# Timed_Power_Switch.net
KiCad netlist of a schematic drawn in Altium Designer
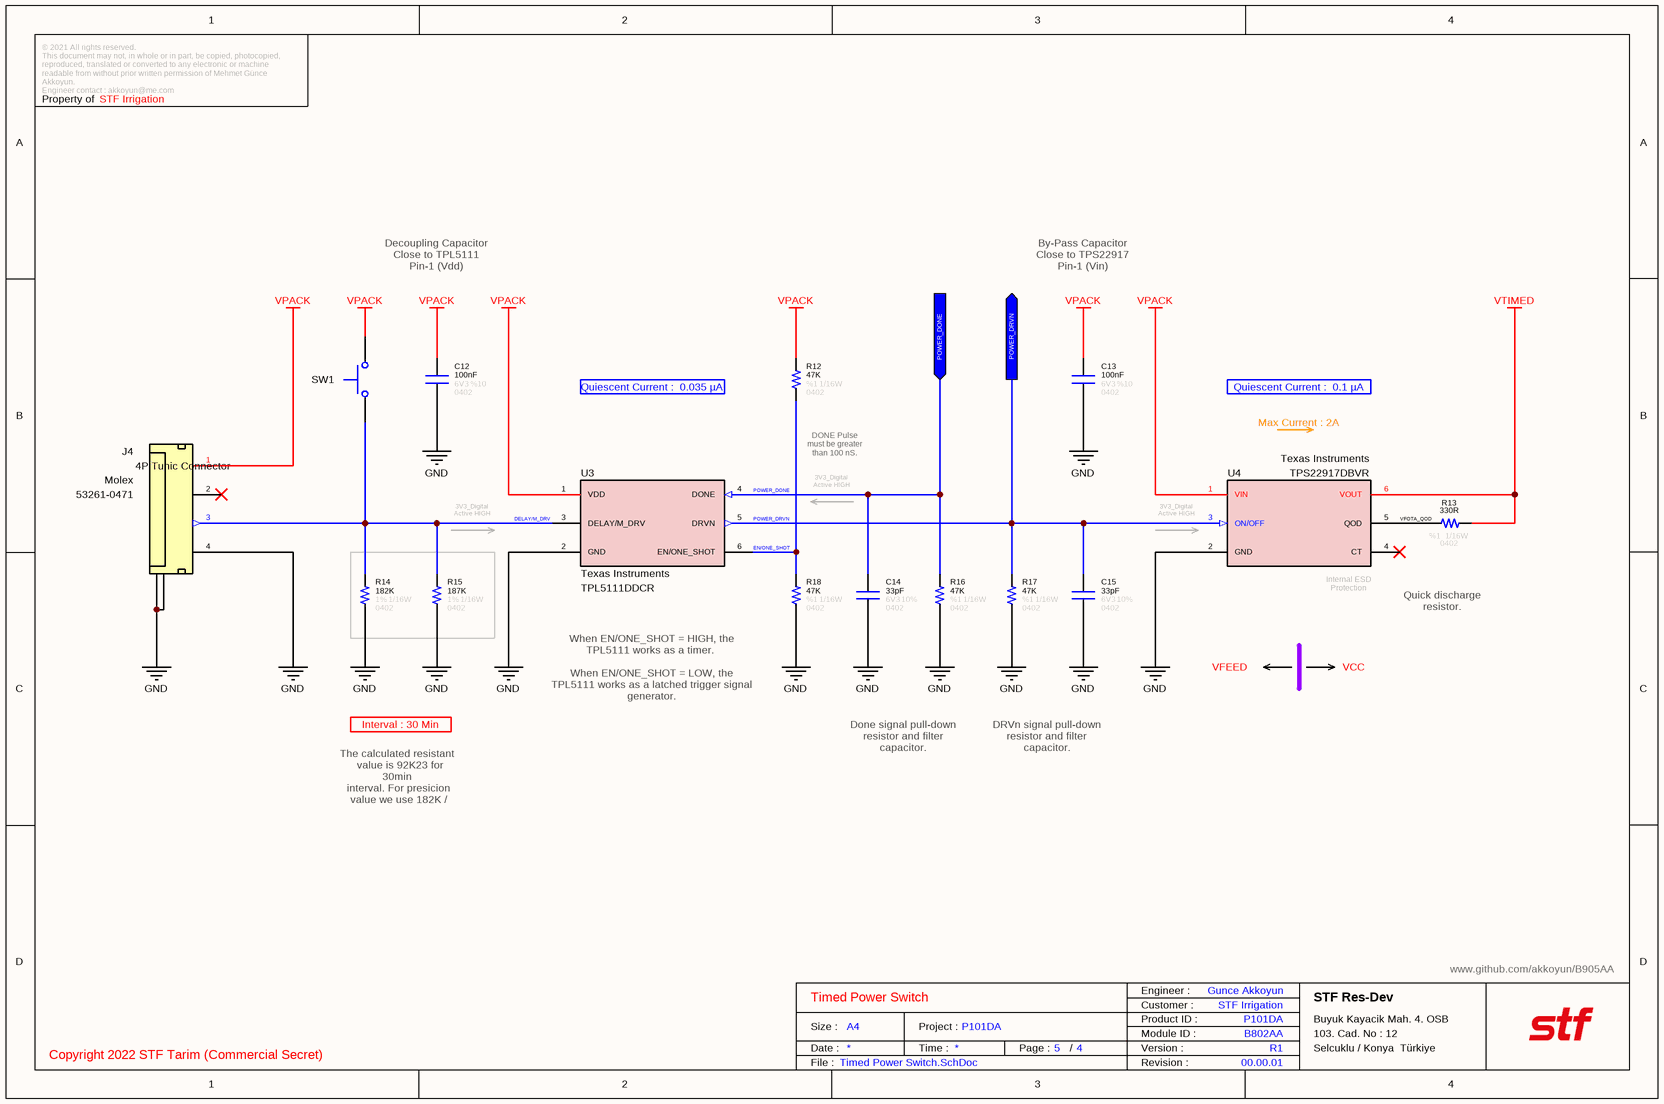
[diagram p0: Timed Power Switch.SchDoc]

(export (version "E")
  (design (tool "Eeschema 10.0.6"))
  (components
    (comp (ref "C12")
      (value "100nF")
      (footprint "CAPACITOR_0402")
      (description "Capacitor - 100nF [0402-6V3] (Ceramic)")
      (fields
        (field (name "MANUFACTURER PART NUMBER") "04026D104KAT4A")
        (field (name "TOLERANCE") "%10")
        (field (name "VOLTAGE") "6V3")
        (field (name "CASE") "0402")
        (field (name "Comment") "Capacitor - 100nF [0402] (Ceramic)")
      )
      (libsource (lib "P101DA_Library") (part "Capacitor - 100nF [0402-6V3]"))
    )
    (comp (ref "C13")
      (value "100nF")
      (footprint "CAPACITOR_0402")
      (description "Capacitor - 100nF [0402-6V3] (Ceramic)")
      (fields
        (field (name "MANUFACTURER PART NUMBER") "04026D104KAT4A")
        (field (name "TOLERANCE") "%10")
        (field (name "VOLTAGE") "6V3")
        (field (name "CASE") "0402")
        (field (name "Comment") "Capacitor - 100nF [0402] (Ceramic)")
      )
      (libsource (lib "P101DA_Library") (part "Capacitor - 100nF [0402-6V3]"))
    )
    (comp (ref "C14")
      (value "33pF")
      (footprint "CAPACITOR_0402")
      (description "Capacitor - 33pF [0402] (Ceramic)")
      (fields
        (field (name "MANUFACTURER PART NUMBER") "C0402C330J9RACAUTO")
        (field (name "TOLERANCE") "10%")
        (field (name "CASE") "0402")
        (field (name "VOLTAGE") "6V3")
      )
      (libsource (lib "P101DA_Library") (part "Capacitor - 33pF [0402-6V3]"))
    )
    (comp (ref "C15")
      (value "33pF")
      (footprint "CAPACITOR_0402")
      (description "Capacitor - 33pF [0402] (Ceramic)")
      (fields
        (field (name "MANUFACTURER PART NUMBER") "C0402C330J9RACAUTO")
        (field (name "TOLERANCE") "10%")
        (field (name "CASE") "0402")
        (field (name "VOLTAGE") "6V3")
      )
      (libsource (lib "P101DA_Library") (part "Capacitor - 33pF [0402-6V3]"))
    )
    (comp (ref "J4")
      (value "4P SMD Tunic Connector")
      (footprint "Connector_Tunic 4P")
      (description "Mini Tunic Connector with 4P")
      (fields
        (field (name "MANUFACTURER NAME") "Molex")
        (field (name "MANUFACTURER PART NUMBER") "53261-0471")
      )
      (libsource (lib "P101DA_Library") (part "Connector - Mini Tunic 4P (1.25)"))
    )
    (comp (ref "R12")
      (value "47K")
      (footprint "RESISTOR_0402")
      (description "Thick Film Resistors - SMD 1/16 W 47 KOhm 1%")
      (fields
        (field (name "MANUFACTURER PART NUMBER") "CRCW040247K0FKED")
        (field (name "TOLERANCE") "%1")
        (field (name "CASE") "0402")
        (field (name "POWER") "1/16W")
        (field (name "Comment") "47K - 0402 - %1 - 1/16W")
      )
      (libsource (lib "P101DA_Library") (part "Resistor - 47K [0402]"))
    )
    (comp (ref "R13")
      (value "330R")
      (footprint "RESISTOR_0402")
      (description "Thick Film Resistors - SMD 1/16 W 330 Ohm 1%")
      (fields
        (field (name "MANUFACTURER PART NUMBER") "CRCW0402330RFKED")
        (field (name "CASE") "0402")
        (field (name "TOLERANCE") "%1")
        (field (name "POWER") "1/16W")
        (field (name "Comment") "330R - 0402 - %1 - 1/16W")
      )
      (libsource (lib "P101DA_Library") (part "Resistor - 330R [0402]"))
    )
    (comp (ref "R14")
      (value "182K")
      (footprint "RESISTOR_0402")
      (description "Thick Film Resistors - SMD 1/16 W 182 KOhm 1%")
      (fields
        (field (name "MANUFACTURER PART NUMBER") "CRCW0402182KFKEDC")
        (field (name "POWER") "1/16W")
        (field (name "CASE") "0402")
        (field (name "TOLERANCE") "1%")
        (field (name "Comment") "182K - 0402 - %1 - 1/16W")
      )
      (libsource (lib "P101DA_Library") (part "Resistor - 182K [0402]"))
    )
    (comp (ref "R15")
      (value "187K")
      (footprint "RESISTOR_0402")
      (description "Thick Film Resistors - SMD 1/16 W 187 KOhm 1%")
      (fields
        (field (name "MANUFACTURER PART NUMBER") "CRCW0402182KFKEDC")
        (field (name "POWER") "1/16W")
        (field (name "CASE") "0402")
        (field (name "TOLERANCE") "1%")
        (field (name "Comment") "187K - 0402 - %1 - 1/16W")
      )
      (libsource (lib "P101DA_Library") (part "Resistor - 187K [0402]"))
    )
    (comp (ref "R16")
      (value "47K")
      (footprint "RESISTOR_0402")
      (description "Thick Film Resistors - SMD 1/16 W 47 KOhm 1%")
      (fields
        (field (name "MANUFACTURER PART NUMBER") "CRCW040247K0FKED")
        (field (name "TOLERANCE") "%1")
        (field (name "CASE") "0402")
        (field (name "POWER") "1/16W")
        (field (name "Comment") "47K - 0402 - %1 - 1/16W")
      )
      (libsource (lib "P101DA_Library") (part "Resistor - 47K [0402]"))
    )
    (comp (ref "R17")
      (value "47K")
      (footprint "RESISTOR_0402")
      (description "Thick Film Resistors - SMD 1/16 W 47 KOhm 1%")
      (fields
        (field (name "MANUFACTURER PART NUMBER") "CRCW040247K0FKED")
        (field (name "TOLERANCE") "%1")
        (field (name "CASE") "0402")
        (field (name "POWER") "1/16W")
        (field (name "Comment") "47K - 0402 - %1 - 1/16W")
      )
      (libsource (lib "P101DA_Library") (part "Resistor - 47K [0402]"))
    )
    (comp (ref "R18")
      (value "47K")
      (footprint "RESISTOR_0402")
      (description "Thick Film Resistors - SMD 1/16 W 47 KOhm 1%")
      (fields
        (field (name "MANUFACTURER PART NUMBER") "CRCW040247K0FKED")
        (field (name "TOLERANCE") "%1")
        (field (name "CASE") "0402")
        (field (name "POWER") "1/16W")
        (field (name "Comment") "47K - 0402 - %1 - 1/16W")
      )
      (libsource (lib "P101DA_Library") (part "Resistor - 47K [0402]"))
    )
    (comp (ref "SW1")
      (value "PTS526SK08SMTR2LFS")
      (footprint "PTS526_Switch")
      (description "Switch Tactile N.O. SPST Flush Round Button Gull Wing 0.05A 12VDC 200000Cycles 2.45N SMD T/R")
      (libsource (lib "P101DA_Library") (part "Switch - Push Button"))
    )
    (comp (ref "U3")
      (value "TPL5111DDCR")
      (footprint "SOT-23-6")
      (description "NANO-POWER SYSTEM TIMER FOR POWE")
      (fields
        (field (name "MANUFACTURER NAME") "Texas Instruments")
        (field (name "MANUFACTURER PART NUMBER") "TPL5111DDCR")
      )
      (libsource (lib "P101DA_Library") (part "IC - TPL5111"))
    )
    (comp (ref "U4")
      (value "Power Switch")
      (footprint "SOT-23-6")
      (description "Power Switch MosFet")
      (fields
        (field (name "MANUFACTURER PART NUMBER") "TPS22917DBVR")
        (field (name "MANUFACTURER NAME") "Texas Instruments")
      )
      (libsource (lib "P101DA_Library") (part "IC - TPS22917"))
    )
  )
  (nets
    (net (code "1") (name "/DELAY{slash}M_DRV") (class "Default")
      (node (ref "J4") (pin "3") (pinfunction "Pin-3_3") (pintype "output"))
      (node (ref "R14") (pin "2") (pinfunction "2_2") (pintype "passive"))
      (node (ref "R15") (pin "2") (pinfunction "2_2") (pintype "passive"))
      (node (ref "SW1") (pin "1") (pinfunction "NC_1") (pintype "passive"))
      (node (ref "U3") (pin "3") (pinfunction "DELAY/M_DRV_3") (pintype "passive"))
    )
    (net (code "2") (name "/EN{slash}ONE_SHOT") (class "Default")
      (node (ref "R12") (pin "1") (pinfunction "1_1") (pintype "passive"))
      (node (ref "R18") (pin "2") (pinfunction "2_2") (pintype "passive"))
      (node (ref "U3") (pin "6") (pinfunction "EN/ONE_SHOT_6") (pintype "passive"))
    )
    (net (code "3") (name "/POWER_DONE") (class "Default")
      (node (ref "C14") (pin "2") (pinfunction "2_2") (pintype "passive"))
      (node (ref "R16") (pin "2") (pinfunction "2_2") (pintype "passive"))
      (node (ref "U3") (pin "4") (pinfunction "DONE_4") (pintype "input"))
    )
    (net (code "4") (name "/POWER_DRVN") (class "Default")
      (node (ref "C15") (pin "2") (pinfunction "2_2") (pintype "passive"))
      (node (ref "R17") (pin "2") (pinfunction "2_2") (pintype "passive"))
      (node (ref "U3") (pin "5") (pinfunction "DRVN_5") (pintype "output"))
      (node (ref "U4") (pin "3") (pinfunction "ON/OFF_3") (pintype "input"))
    )
    (net (code "5") (name "/VFOTA_QOD") (class "Default")
      (node (ref "R13") (pin "2") (pinfunction "2_2") (pintype "passive"))
      (node (ref "U4") (pin "5") (pinfunction "QOD_5") (pintype "power_in"))
    )
    (net (code "6") (name "GND") (class "Default")
      (node (ref "C12") (pin "1") (pinfunction "1_1") (pintype "passive"))
      (node (ref "C13") (pin "1") (pinfunction "1_1") (pintype "passive"))
      (node (ref "C14") (pin "1") (pinfunction "1_1") (pintype "passive"))
      (node (ref "C15") (pin "1") (pinfunction "1_1") (pintype "passive"))
      (node (ref "J4") (pin "4") (pinfunction "Pin-4_4") (pintype "power_in"))
      (node (ref "J4") (pin "5") (pinfunction "GND_5") (pintype "passive"))
      (node (ref "J4") (pin "6") (pinfunction "GND_6") (pintype "passive"))
      (node (ref "R14") (pin "1") (pinfunction "1_1") (pintype "passive"))
      (node (ref "R15") (pin "1") (pinfunction "1_1") (pintype "passive"))
      (node (ref "R16") (pin "1") (pinfunction "1_1") (pintype "passive"))
      (node (ref "R17") (pin "1") (pinfunction "1_1") (pintype "passive"))
      (node (ref "R18") (pin "1") (pinfunction "1_1") (pintype "passive"))
      (node (ref "U3") (pin "2") (pinfunction "GND_2") (pintype "power_in"))
      (node (ref "U4") (pin "2") (pinfunction "GND_2") (pintype "power_in"))
    )
    (net (code "7") (name "VPACK") (class "Default")
      (node (ref "C12") (pin "2") (pinfunction "2_2") (pintype "passive"))
      (node (ref "C13") (pin "2") (pinfunction "2_2") (pintype "passive"))
      (node (ref "J4") (pin "1") (pinfunction "Pin-1_1") (pintype "power_in"))
      (node (ref "R12") (pin "2") (pinfunction "2_2") (pintype "passive"))
      (node (ref "SW1") (pin "2") (pinfunction "COM_2") (pintype "passive"))
      (node (ref "U3") (pin "1") (pinfunction "VDD_1") (pintype "power_in"))
      (node (ref "U4") (pin "1") (pinfunction "VIN_1") (pintype "power_in"))
    )
    (net (code "8") (name "VTIMED") (class "Default")
      (node (ref "R13") (pin "1") (pinfunction "1_1") (pintype "passive"))
      (node (ref "U4") (pin "6") (pinfunction "VOUT_6") (pintype "power_in"))
    )
    (net (code "9") (name "unconnected-(J4-Pin-2-Pad2)") (class "Default")
      (node (ref "J4") (pin "2") (pinfunction "Pin-2_2") (pintype "passive+no_connect"))
    )
    (net (code "10") (name "unconnected-(U4-CT-Pad4)") (class "Default")
      (node (ref "U4") (pin "4") (pinfunction "CT_4") (pintype "power_in+no_connect"))
    )
  )
)
